# 7seg.net
KiCad netlist of a schematic drawn in Altium Designer
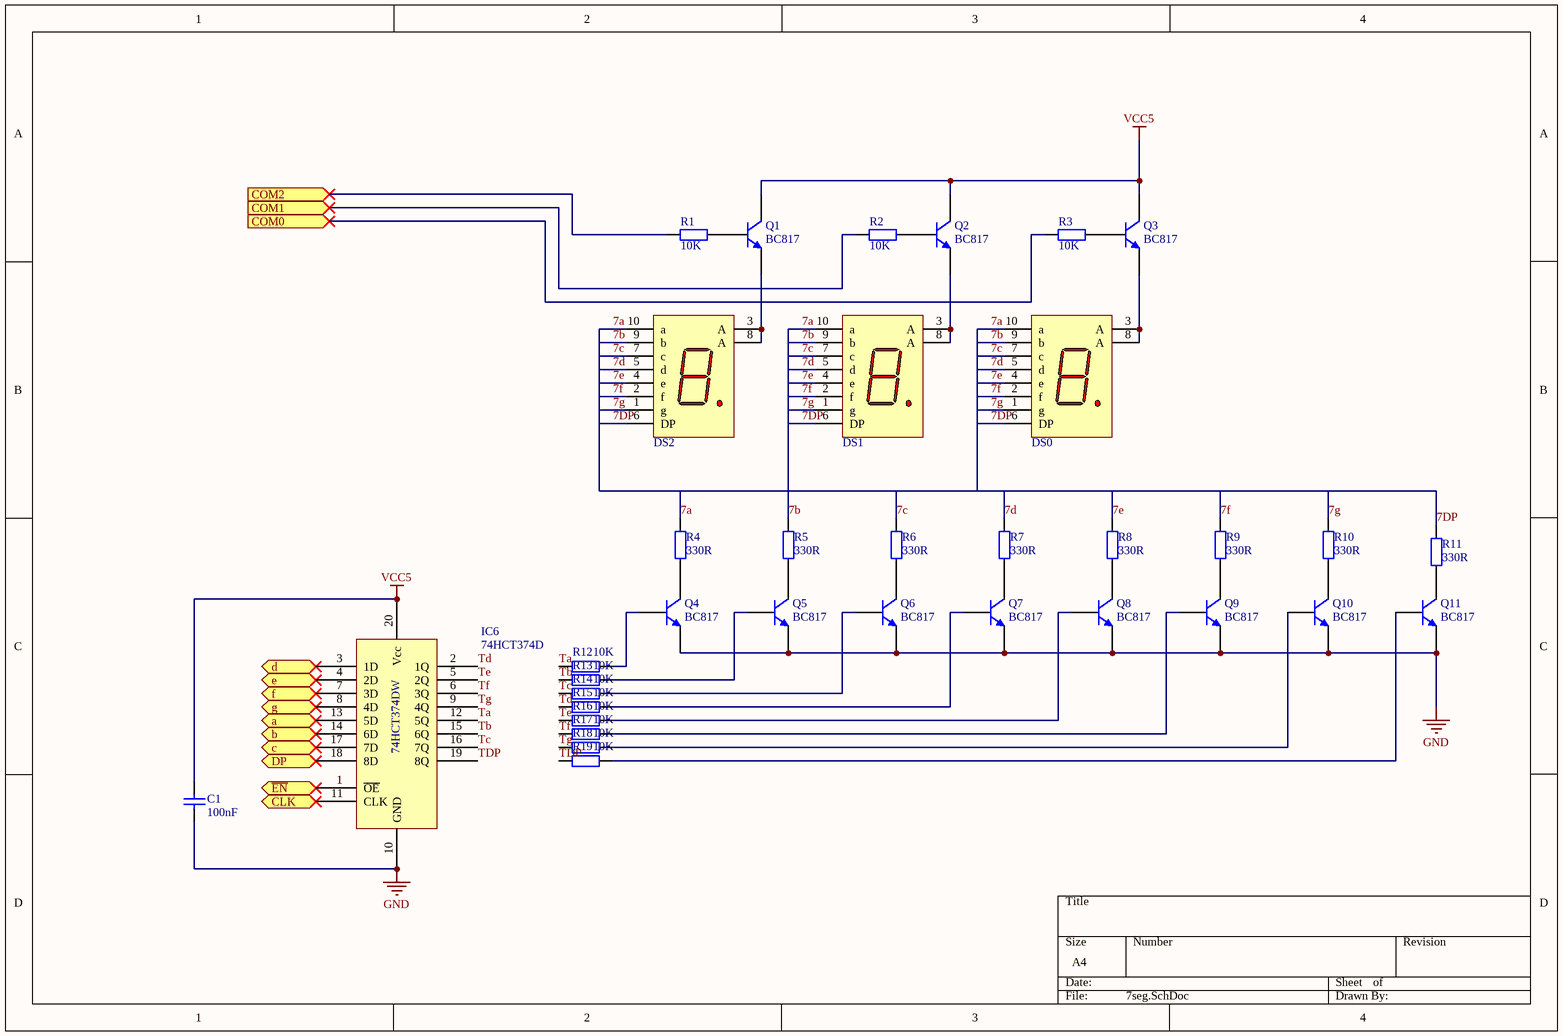
[diagram p0: 7seg.SchDoc]

(export (version "E")
  (design (tool "Eeschema 10.0.6"))
  (components
    (comp (ref "C1")
      (value "100nF")
      (footprint "FP_0805_CAP_085")
      (description "Capacitor")
      (fields (field (name "TOLERANCE") "+80%/-20%") (field (name "VOLTAGE") "25V"))
      (libsource (lib "hallglib") (part "CAP 100nF"))
    )
    (comp (ref "DS0")
      (value "7SEG")
      (footprint "FP_7SEG")
      (description "Common Anode 7 Segment Display")
      (libsource (lib "hallglib") (part "7SEG"))
    )
    (comp (ref "DS1")
      (value "7SEG")
      (footprint "FP_7SEG")
      (description "Common Anode 7 Segment Display")
      (libsource (lib "hallglib") (part "7SEG"))
    )
    (comp (ref "DS2")
      (value "7SEG")
      (footprint "FP_7SEG")
      (description "Common Anode 7 Segment Display")
      (libsource (lib "hallglib") (part "7SEG"))
    )
    (comp (ref "IC6") (value "74HCT374D") (footprint "SOP20") (libsource (lib "iao0w2") (part "74HCT374D")))
    (comp (ref "Q1")
      (value "BC817")
      (footprint "FP_SOT23-3")
      (description "NPN Transistor")
      (libsource (lib "hallglib") (part "BC817"))
    )
    (comp (ref "Q2")
      (value "BC817")
      (footprint "FP_SOT23-3")
      (description "NPN Transistor")
      (libsource (lib "hallglib") (part "BC817"))
    )
    (comp (ref "Q3")
      (value "BC817")
      (footprint "FP_SOT23-3")
      (description "NPN Transistor")
      (libsource (lib "hallglib") (part "BC817"))
    )
    (comp (ref "Q4")
      (value "BC817")
      (footprint "FP_SOT23-3")
      (description "NPN Transistor")
      (libsource (lib "hallglib") (part "BC817"))
    )
    (comp (ref "Q5")
      (value "BC817")
      (footprint "FP_SOT23-3")
      (description "NPN Transistor")
      (libsource (lib "hallglib") (part "BC817"))
    )
    (comp (ref "Q6")
      (value "BC817")
      (footprint "FP_SOT23-3")
      (description "NPN Transistor")
      (libsource (lib "hallglib") (part "BC817"))
    )
    (comp (ref "Q7")
      (value "BC817")
      (footprint "FP_SOT23-3")
      (description "NPN Transistor")
      (libsource (lib "hallglib") (part "BC817"))
    )
    (comp (ref "Q8")
      (value "BC817")
      (footprint "FP_SOT23-3")
      (description "NPN Transistor")
      (libsource (lib "hallglib") (part "BC817"))
    )
    (comp (ref "Q9")
      (value "BC817")
      (footprint "FP_SOT23-3")
      (description "NPN Transistor")
      (libsource (lib "hallglib") (part "BC817"))
    )
    (comp (ref "Q10")
      (value "BC817")
      (footprint "FP_SOT23-3")
      (description "NPN Transistor")
      (libsource (lib "hallglib") (part "BC817"))
    )
    (comp (ref "Q11")
      (value "BC817")
      (footprint "FP_SOT23-3")
      (description "NPN Transistor")
      (libsource (lib "hallglib") (part "BC817"))
    )
    (comp (ref "R1")
      (value "10K")
      (footprint "FP_0805_RES")
      (description "Resistor")
      (fields (field (name "TOLERANCE") "5%") (field (name "POWER") "125mW"))
      (libsource (lib "hallglib") (part "RES 10K"))
    )
    (comp (ref "R2")
      (value "10K")
      (footprint "FP_0805_RES")
      (description "Resistor")
      (fields (field (name "TOLERANCE") "5%") (field (name "POWER") "125mW"))
      (libsource (lib "hallglib") (part "RES 10K"))
    )
    (comp (ref "R3")
      (value "10K")
      (footprint "FP_0805_RES")
      (description "Resistor")
      (fields (field (name "TOLERANCE") "5%") (field (name "POWER") "125mW"))
      (libsource (lib "hallglib") (part "RES 10K"))
    )
    (comp (ref "R4")
      (value "330R")
      (footprint "FP_0805_RES")
      (description "Resistor")
      (fields (field (name "TOLERANCE") "5%") (field (name "POWER") "125mW"))
      (libsource (lib "hallglib") (part "RES 330R"))
    )
    (comp (ref "R5")
      (value "330R")
      (footprint "FP_0805_RES")
      (description "Resistor")
      (fields (field (name "TOLERANCE") "5%") (field (name "POWER") "125mW"))
      (libsource (lib "hallglib") (part "RES 330R"))
    )
    (comp (ref "R6")
      (value "330R")
      (footprint "FP_0805_RES")
      (description "Resistor")
      (fields (field (name "TOLERANCE") "5%") (field (name "POWER") "125mW"))
      (libsource (lib "hallglib") (part "RES 330R"))
    )
    (comp (ref "R7")
      (value "330R")
      (footprint "FP_0805_RES")
      (description "Resistor")
      (fields (field (name "TOLERANCE") "5%") (field (name "POWER") "125mW"))
      (libsource (lib "hallglib") (part "RES 330R"))
    )
    (comp (ref "R8")
      (value "330R")
      (footprint "FP_0805_RES")
      (description "Resistor")
      (fields (field (name "TOLERANCE") "5%") (field (name "POWER") "125mW"))
      (libsource (lib "hallglib") (part "RES 330R"))
    )
    (comp (ref "R9")
      (value "330R")
      (footprint "FP_0805_RES")
      (description "Resistor")
      (fields (field (name "TOLERANCE") "5%") (field (name "POWER") "125mW"))
      (libsource (lib "hallglib") (part "RES 330R"))
    )
    (comp (ref "R10")
      (value "330R")
      (footprint "FP_0805_RES")
      (description "Resistor")
      (fields (field (name "TOLERANCE") "5%") (field (name "POWER") "125mW"))
      (libsource (lib "hallglib") (part "RES 330R"))
    )
    (comp (ref "R11")
      (value "330R")
      (footprint "FP_0805_RES")
      (description "Resistor")
      (fields (field (name "TOLERANCE") "5%") (field (name "POWER") "125mW"))
      (libsource (lib "hallglib") (part "RES 330R"))
    )
    (comp (ref "R12")
      (value "10K")
      (footprint "FP_0805_RES")
      (description "Resistor")
      (fields (field (name "TOLERANCE") "5%") (field (name "POWER") "125mW"))
      (libsource (lib "hallglib") (part "RES 10K"))
    )
    (comp (ref "R13")
      (value "10K")
      (footprint "FP_0805_RES")
      (description "Resistor")
      (fields (field (name "TOLERANCE") "5%") (field (name "POWER") "125mW"))
      (libsource (lib "hallglib") (part "RES 10K"))
    )
    (comp (ref "R14")
      (value "10K")
      (footprint "FP_0805_RES")
      (description "Resistor")
      (fields (field (name "TOLERANCE") "5%") (field (name "POWER") "125mW"))
      (libsource (lib "hallglib") (part "RES 10K"))
    )
    (comp (ref "R15")
      (value "10K")
      (footprint "FP_0805_RES")
      (description "Resistor")
      (fields (field (name "TOLERANCE") "5%") (field (name "POWER") "125mW"))
      (libsource (lib "hallglib") (part "RES 10K"))
    )
    (comp (ref "R16")
      (value "10K")
      (footprint "FP_0805_RES")
      (description "Resistor")
      (fields (field (name "TOLERANCE") "5%") (field (name "POWER") "125mW"))
      (libsource (lib "hallglib") (part "RES 10K"))
    )
    (comp (ref "R17")
      (value "10K")
      (footprint "FP_0805_RES")
      (description "Resistor")
      (fields (field (name "TOLERANCE") "5%") (field (name "POWER") "125mW"))
      (libsource (lib "hallglib") (part "RES 10K"))
    )
    (comp (ref "R18")
      (value "10K")
      (footprint "FP_0805_RES")
      (description "Resistor")
      (fields (field (name "TOLERANCE") "5%") (field (name "POWER") "125mW"))
      (libsource (lib "hallglib") (part "RES 10K"))
    )
    (comp (ref "R19")
      (value "10K")
      (footprint "FP_0805_RES")
      (description "Resistor")
      (fields (field (name "TOLERANCE") "5%") (field (name "POWER") "125mW"))
      (libsource (lib "hallglib") (part "RES 10K"))
    )
  )
  (nets
    (net (code "1") (name "/7DP") (class "Default")
      (node (ref "DS0") (pin "6") (pinfunction "DP_6") (pintype "passive"))
      (node (ref "DS1") (pin "6") (pinfunction "DP_6") (pintype "passive"))
      (node (ref "DS2") (pin "6") (pinfunction "DP_6") (pintype "passive"))
      (node (ref "R11") (pin "2") (pinfunction "2_2") (pintype "passive"))
    )
    (net (code "2") (name "/7a") (class "Default")
      (node (ref "DS0") (pin "10") (pinfunction "a_10") (pintype "passive"))
      (node (ref "DS1") (pin "10") (pinfunction "a_10") (pintype "passive"))
      (node (ref "DS2") (pin "10") (pinfunction "a_10") (pintype "passive"))
      (node (ref "R4") (pin "2") (pinfunction "2_2") (pintype "passive"))
    )
    (net (code "3") (name "/7b") (class "Default")
      (node (ref "DS0") (pin "9") (pinfunction "b_9") (pintype "passive"))
      (node (ref "DS1") (pin "9") (pinfunction "b_9") (pintype "passive"))
      (node (ref "DS2") (pin "9") (pinfunction "b_9") (pintype "passive"))
      (node (ref "R5") (pin "2") (pinfunction "2_2") (pintype "passive"))
    )
    (net (code "4") (name "/7c") (class "Default")
      (node (ref "DS0") (pin "7") (pinfunction "c_7") (pintype "passive"))
      (node (ref "DS1") (pin "7") (pinfunction "c_7") (pintype "passive"))
      (node (ref "DS2") (pin "7") (pinfunction "c_7") (pintype "passive"))
      (node (ref "R6") (pin "2") (pinfunction "2_2") (pintype "passive"))
    )
    (net (code "5") (name "/7d") (class "Default")
      (node (ref "DS0") (pin "5") (pinfunction "d_5") (pintype "passive"))
      (node (ref "DS1") (pin "5") (pinfunction "d_5") (pintype "passive"))
      (node (ref "DS2") (pin "5") (pinfunction "d_5") (pintype "passive"))
      (node (ref "R7") (pin "2") (pinfunction "2_2") (pintype "passive"))
    )
    (net (code "6") (name "/7e") (class "Default")
      (node (ref "DS0") (pin "4") (pinfunction "e_4") (pintype "passive"))
      (node (ref "DS1") (pin "4") (pinfunction "e_4") (pintype "passive"))
      (node (ref "DS2") (pin "4") (pinfunction "e_4") (pintype "passive"))
      (node (ref "R8") (pin "2") (pinfunction "2_2") (pintype "passive"))
    )
    (net (code "7") (name "/7f") (class "Default")
      (node (ref "DS0") (pin "2") (pinfunction "f_2") (pintype "passive"))
      (node (ref "DS1") (pin "2") (pinfunction "f_2") (pintype "passive"))
      (node (ref "DS2") (pin "2") (pinfunction "f_2") (pintype "passive"))
      (node (ref "R9") (pin "2") (pinfunction "2_2") (pintype "passive"))
    )
    (net (code "8") (name "/7g") (class "Default")
      (node (ref "DS0") (pin "1") (pinfunction "g_1") (pintype "passive"))
      (node (ref "DS1") (pin "1") (pinfunction "g_1") (pintype "passive"))
      (node (ref "DS2") (pin "1") (pinfunction "g_1") (pintype "passive"))
      (node (ref "R10") (pin "2") (pinfunction "2_2") (pintype "passive"))
    )
    (net (code "9") (name "/CLK") (class "Default")
      (node (ref "IC6") (pin "11") (pinfunction "CLK_11") (pintype "passive+no_connect"))
    )
    (net (code "10") (name "/COM0") (class "Default")
      (node (ref "R3") (pin "1") (pinfunction "1_1") (pintype "passive+no_connect"))
    )
    (net (code "11") (name "/COM1") (class "Default")
      (node (ref "R2") (pin "1") (pinfunction "1_1") (pintype "passive+no_connect"))
    )
    (net (code "12") (name "/COM2") (class "Default")
      (node (ref "R1") (pin "1") (pinfunction "1_1") (pintype "passive+no_connect"))
    )
    (net (code "13") (name "/DP") (class "Default")
      (node (ref "IC6") (pin "18") (pinfunction "8D_18") (pintype "passive+no_connect"))
    )
    (net (code "14") (name "/TDP") (class "Default")
      (node (ref "IC6") (pin "19") (pinfunction "8Q_19") (pintype "passive"))
      (node (ref "R19") (pin "1") (pinfunction "1_1") (pintype "passive"))
    )
    (net (code "15") (name "/Ta") (class "Default")
      (node (ref "IC6") (pin "12") (pinfunction "5Q_12") (pintype "passive"))
      (node (ref "R12") (pin "1") (pinfunction "1_1") (pintype "passive"))
    )
    (net (code "16") (name "/Tb") (class "Default")
      (node (ref "IC6") (pin "15") (pinfunction "6Q_15") (pintype "passive"))
      (node (ref "R13") (pin "1") (pinfunction "1_1") (pintype "passive"))
    )
    (net (code "17") (name "/Tc") (class "Default")
      (node (ref "IC6") (pin "16") (pinfunction "7Q_16") (pintype "passive"))
      (node (ref "R14") (pin "1") (pinfunction "1_1") (pintype "passive"))
    )
    (net (code "18") (name "/Td") (class "Default")
      (node (ref "IC6") (pin "2") (pinfunction "1Q_2") (pintype "passive"))
      (node (ref "R15") (pin "1") (pinfunction "1_1") (pintype "passive"))
    )
    (net (code "19") (name "/Te") (class "Default")
      (node (ref "IC6") (pin "5") (pinfunction "2Q_5") (pintype "passive"))
      (node (ref "R16") (pin "1") (pinfunction "1_1") (pintype "passive"))
    )
    (net (code "20") (name "/Tf") (class "Default")
      (node (ref "IC6") (pin "6") (pinfunction "3Q_6") (pintype "passive"))
      (node (ref "R17") (pin "1") (pinfunction "1_1") (pintype "passive"))
    )
    (net (code "21") (name "/Tg") (class "Default")
      (node (ref "IC6") (pin "9") (pinfunction "4Q_9") (pintype "passive"))
      (node (ref "R18") (pin "1") (pinfunction "1_1") (pintype "passive"))
    )
    (net (code "22") (name "/a") (class "Default")
      (node (ref "IC6") (pin "13") (pinfunction "5D_13") (pintype "passive+no_connect"))
    )
    (net (code "23") (name "/b") (class "Default")
      (node (ref "IC6") (pin "14") (pinfunction "6D_14") (pintype "passive+no_connect"))
    )
    (net (code "24") (name "/c") (class "Default")
      (node (ref "IC6") (pin "17") (pinfunction "7D_17") (pintype "passive+no_connect"))
    )
    (net (code "25") (name "/d") (class "Default")
      (node (ref "IC6") (pin "3") (pinfunction "1D_3") (pintype "passive+no_connect"))
    )
    (net (code "26") (name "/e") (class "Default")
      (node (ref "IC6") (pin "4") (pinfunction "2D_4") (pintype "passive+no_connect"))
    )
    (net (code "27") (name "/f") (class "Default")
      (node (ref "IC6") (pin "7") (pinfunction "3D_7") (pintype "passive+no_connect"))
    )
    (net (code "28") (name "/g") (class "Default")
      (node (ref "IC6") (pin "8") (pinfunction "4D_8") (pintype "passive+no_connect"))
    )
    (net (code "29") (name "/~{EN}") (class "Default")
      (node (ref "IC6") (pin "1") (pinfunction "~{OE}_1") (pintype "passive+no_connect"))
    )
    (net (code "30") (name "GND") (class "Default")
      (node (ref "C1") (pin "1") (pinfunction "1_1") (pintype "passive"))
      (node (ref "IC6") (pin "10") (pinfunction "GND_10") (pintype "passive"))
      (node (ref "Q10") (pin "1") (pinfunction "E_1") (pintype "passive"))
      (node (ref "Q11") (pin "1") (pinfunction "E_1") (pintype "passive"))
      (node (ref "Q4") (pin "1") (pinfunction "E_1") (pintype "passive"))
      (node (ref "Q5") (pin "1") (pinfunction "E_1") (pintype "passive"))
      (node (ref "Q6") (pin "1") (pinfunction "E_1") (pintype "passive"))
      (node (ref "Q7") (pin "1") (pinfunction "E_1") (pintype "passive"))
      (node (ref "Q8") (pin "1") (pinfunction "E_1") (pintype "passive"))
      (node (ref "Q9") (pin "1") (pinfunction "E_1") (pintype "passive"))
    )
    (net (code "31") (name "Net-(Q1-B)") (class "Default")
      (node (ref "Q1") (pin "2") (pinfunction "B_2") (pintype "passive"))
      (node (ref "R1") (pin "2") (pinfunction "2_2") (pintype "passive"))
    )
    (net (code "32") (name "Net-(Q1-E)") (class "Default")
      (node (ref "DS2") (pin "3") (pinfunction "A_3") (pintype "passive"))
      (node (ref "DS2") (pin "8") (pinfunction "A_8") (pintype "passive"))
      (node (ref "Q1") (pin "1") (pinfunction "E_1") (pintype "passive"))
    )
    (net (code "33") (name "Net-(Q2-B)") (class "Default")
      (node (ref "Q2") (pin "2") (pinfunction "B_2") (pintype "passive"))
      (node (ref "R2") (pin "2") (pinfunction "2_2") (pintype "passive"))
    )
    (net (code "34") (name "Net-(Q2-E)") (class "Default")
      (node (ref "DS1") (pin "3") (pinfunction "A_3") (pintype "passive"))
      (node (ref "DS1") (pin "8") (pinfunction "A_8") (pintype "passive"))
      (node (ref "Q2") (pin "1") (pinfunction "E_1") (pintype "passive"))
    )
    (net (code "35") (name "Net-(Q3-B)") (class "Default")
      (node (ref "Q3") (pin "2") (pinfunction "B_2") (pintype "passive"))
      (node (ref "R3") (pin "2") (pinfunction "2_2") (pintype "passive"))
    )
    (net (code "36") (name "Net-(Q3-E)") (class "Default")
      (node (ref "DS0") (pin "3") (pinfunction "A_3") (pintype "passive"))
      (node (ref "DS0") (pin "8") (pinfunction "A_8") (pintype "passive"))
      (node (ref "Q3") (pin "1") (pinfunction "E_1") (pintype "passive"))
    )
    (net (code "37") (name "Net-(Q4-B)") (class "Default")
      (node (ref "Q4") (pin "2") (pinfunction "B_2") (pintype "passive"))
      (node (ref "R12") (pin "2") (pinfunction "2_2") (pintype "passive"))
    )
    (net (code "38") (name "Net-(Q4-C)") (class "Default")
      (node (ref "Q4") (pin "3") (pinfunction "C_3") (pintype "passive"))
      (node (ref "R4") (pin "1") (pinfunction "1_1") (pintype "passive"))
    )
    (net (code "39") (name "Net-(Q5-B)") (class "Default")
      (node (ref "Q5") (pin "2") (pinfunction "B_2") (pintype "passive"))
      (node (ref "R13") (pin "2") (pinfunction "2_2") (pintype "passive"))
    )
    (net (code "40") (name "Net-(Q5-C)") (class "Default")
      (node (ref "Q5") (pin "3") (pinfunction "C_3") (pintype "passive"))
      (node (ref "R5") (pin "1") (pinfunction "1_1") (pintype "passive"))
    )
    (net (code "41") (name "Net-(Q6-B)") (class "Default")
      (node (ref "Q6") (pin "2") (pinfunction "B_2") (pintype "passive"))
      (node (ref "R14") (pin "2") (pinfunction "2_2") (pintype "passive"))
    )
    (net (code "42") (name "Net-(Q6-C)") (class "Default")
      (node (ref "Q6") (pin "3") (pinfunction "C_3") (pintype "passive"))
      (node (ref "R6") (pin "1") (pinfunction "1_1") (pintype "passive"))
    )
    (net (code "43") (name "Net-(Q7-B)") (class "Default")
      (node (ref "Q7") (pin "2") (pinfunction "B_2") (pintype "passive"))
      (node (ref "R15") (pin "2") (pinfunction "2_2") (pintype "passive"))
    )
    (net (code "44") (name "Net-(Q7-C)") (class "Default")
      (node (ref "Q7") (pin "3") (pinfunction "C_3") (pintype "passive"))
      (node (ref "R7") (pin "1") (pinfunction "1_1") (pintype "passive"))
    )
    (net (code "45") (name "Net-(Q8-B)") (class "Default")
      (node (ref "Q8") (pin "2") (pinfunction "B_2") (pintype "passive"))
      (node (ref "R16") (pin "2") (pinfunction "2_2") (pintype "passive"))
    )
    (net (code "46") (name "Net-(Q8-C)") (class "Default")
      (node (ref "Q8") (pin "3") (pinfunction "C_3") (pintype "passive"))
      (node (ref "R8") (pin "1") (pinfunction "1_1") (pintype "passive"))
    )
    (net (code "47") (name "Net-(Q9-B)") (class "Default")
      (node (ref "Q9") (pin "2") (pinfunction "B_2") (pintype "passive"))
      (node (ref "R17") (pin "2") (pinfunction "2_2") (pintype "passive"))
    )
    (net (code "48") (name "Net-(Q9-C)") (class "Default")
      (node (ref "Q9") (pin "3") (pinfunction "C_3") (pintype "passive"))
      (node (ref "R9") (pin "1") (pinfunction "1_1") (pintype "passive"))
    )
    (net (code "49") (name "Net-(Q10-B)") (class "Default")
      (node (ref "Q10") (pin "2") (pinfunction "B_2") (pintype "passive"))
      (node (ref "R18") (pin "2") (pinfunction "2_2") (pintype "passive"))
    )
    (net (code "50") (name "Net-(Q10-C)") (class "Default")
      (node (ref "Q10") (pin "3") (pinfunction "C_3") (pintype "passive"))
      (node (ref "R10") (pin "1") (pinfunction "1_1") (pintype "passive"))
    )
    (net (code "51") (name "Net-(Q11-B)") (class "Default")
      (node (ref "Q11") (pin "2") (pinfunction "B_2") (pintype "passive"))
      (node (ref "R19") (pin "2") (pinfunction "2_2") (pintype "passive"))
    )
    (net (code "52") (name "Net-(Q11-C)") (class "Default")
      (node (ref "Q11") (pin "3") (pinfunction "C_3") (pintype "passive"))
      (node (ref "R11") (pin "1") (pinfunction "1_1") (pintype "passive"))
    )
    (net (code "53") (name "VCC5") (class "Default")
      (node (ref "C1") (pin "2") (pinfunction "2_2") (pintype "passive"))
      (node (ref "IC6") (pin "20") (pinfunction "Vcc_20") (pintype "passive"))
      (node (ref "Q1") (pin "3") (pinfunction "C_3") (pintype "passive"))
      (node (ref "Q2") (pin "3") (pinfunction "C_3") (pintype "passive"))
      (node (ref "Q3") (pin "3") (pinfunction "C_3") (pintype "passive"))
    )
  )
)
